# r3_sch.net
KiCad netlist of a schematic drawn in EAGLE
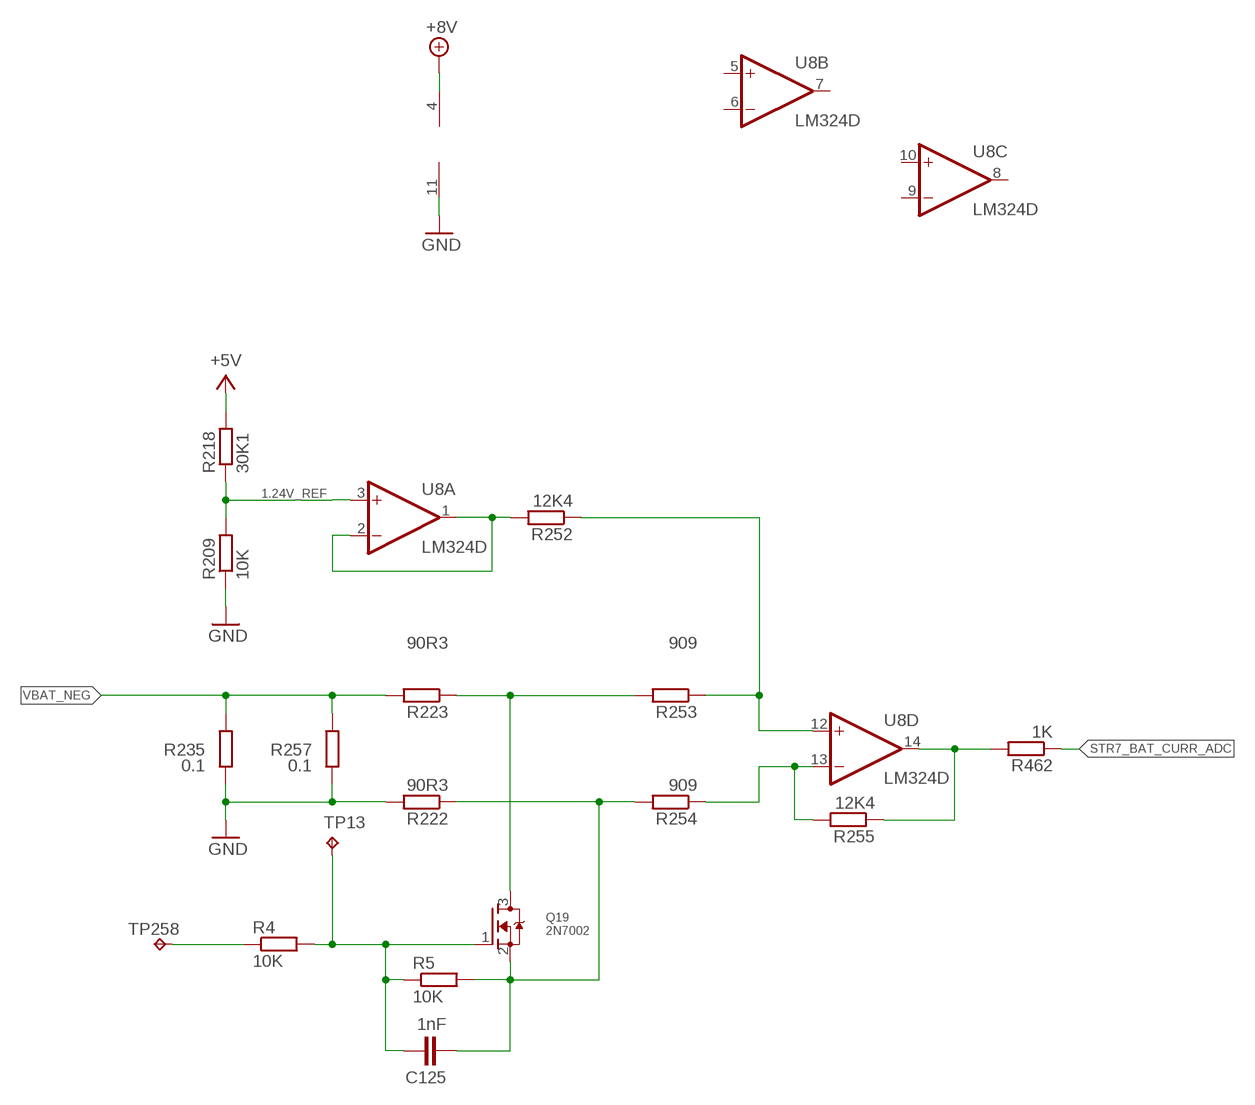
[diagram p0: schematic, sheet 1]

(export (version "E")
  (design (tool "Eeschema 10.0.6"))
  (components
    (comp (ref "C125")
      (value "1nF")
      (footprint "eagle-import:C0603")
      (libsource (lib "eagle-import") (part "C-EUC0603"))
    )
    (comp (ref "Q19")
      (value "2N7002")
      (footprint "eagle-import:SOT23")
      (libsource (lib "eagle-import") (part "MOSFET-NREFLOW"))
    )
    (comp (ref "R4")
      (value "10K")
      (footprint "eagle-import:R0603")
      (libsource (lib "eagle-import") (part "resistor_R-EU_R0603"))
    )
    (comp (ref "R5")
      (value "10K")
      (footprint "eagle-import:R0603")
      (libsource (lib "eagle-import") (part "resistor_R-EU_R0603"))
    )
    (comp (ref "R209")
      (value "10K")
      (footprint "eagle-import:R0603")
      (libsource (lib "eagle-import") (part "resistor_R-EU_R0603"))
    )
    (comp (ref "R218")
      (value "30K1")
      (footprint "eagle-import:R0603")
      (libsource (lib "eagle-import") (part "resistor_R-EU_R0603"))
    )
    (comp (ref "R222")
      (value "90R3")
      (footprint "eagle-import:R0603")
      (libsource (lib "eagle-import") (part "resistor_R-EU_R0603"))
    )
    (comp (ref "R223")
      (value "90R3")
      (footprint "eagle-import:R0603")
      (libsource (lib "eagle-import") (part "resistor_R-EU_R0603"))
    )
    (comp (ref "R235")
      (value "0.1")
      (footprint "eagle-import:R1206")
      (libsource (lib "eagle-import") (part "R-EU_R1206"))
    )
    (comp (ref "R252")
      (value "12K4")
      (footprint "eagle-import:R0603")
      (libsource (lib "eagle-import") (part "resistor_R-EU_R0603"))
    )
    (comp (ref "R253")
      (value "909")
      (footprint "eagle-import:R0603")
      (libsource (lib "eagle-import") (part "resistor_R-EU_R0603"))
    )
    (comp (ref "R254")
      (value "909")
      (footprint "eagle-import:R0603")
      (libsource (lib "eagle-import") (part "resistor_R-EU_R0603"))
    )
    (comp (ref "R255")
      (value "12K4")
      (footprint "eagle-import:R0603")
      (libsource (lib "eagle-import") (part "resistor_R-EU_R0603"))
    )
    (comp (ref "R257")
      (value "0.1")
      (footprint "eagle-import:R1206")
      (libsource (lib "eagle-import") (part "R-EU_R1206"))
    )
    (comp (ref "R462")
      (value "1K")
      (footprint "eagle-import:R0603")
      (libsource (lib "eagle-import") (part "resistor_R-EU_R0603"))
    )
    (comp (ref "TP13")
      (value "TPB1,27")
      (footprint "eagle-import:B1,27")
      (libsource (lib "eagle-import") (part "TPB1,27"))
    )
    (comp (ref "TP258")
      (value "TPB1,27")
      (footprint "eagle-import:B1,27")
      (libsource (lib "eagle-import") (part "TPB1,27"))
    )
    (comp (ref "U8")
      (value "LM324D")
      (footprint "eagle-import:SO14")
      (libsource (lib "eagle-import") (part "LM324D"))
    )
  )
  (nets
    (net (code "1") (name "+5V") (class "Default")
      (node (ref "R218") (pin "2") (pinfunction "2_2") (pintype "passive"))
    )
    (net (code "2") (name "+8V") (class "Default")
      (node (ref "U8") (pin "4") (pinfunction "V+_4") (pintype "power_in"))
    )
    (net (code "3") (name "/1.24V_REF") (class "Default")
      (node (ref "R209") (pin "2") (pinfunction "2_2") (pintype "passive"))
      (node (ref "R218") (pin "1") (pinfunction "1_1") (pintype "passive"))
      (node (ref "U8") (pin "3") (pinfunction "+IN_3") (pintype "input"))
    )
    (net (code "4") (name "GND") (class "Default")
      (node (ref "R209") (pin "1") (pinfunction "1_1") (pintype "passive"))
      (node (ref "R222") (pin "2") (pinfunction "2_2") (pintype "passive"))
      (node (ref "R235") (pin "2") (pinfunction "2_2") (pintype "passive"))
      (node (ref "R257") (pin "2") (pinfunction "2_2") (pintype "passive"))
      (node (ref "U8") (pin "11") (pinfunction "V-_11") (pintype "power_in"))
    )
    (net (code "5") (name "Net-(Q19-D)") (class "Default")
      (node (ref "Q19") (pin "3") (pinfunction "D_3") (pintype "bidirectional"))
      (node (ref "R223") (pin "1") (pinfunction "1_1") (pintype "passive"))
      (node (ref "R253") (pin "2") (pinfunction "2_2") (pintype "passive"))
    )
    (net (code "6") (name "Net-(Q19-G)") (class "Default")
      (node (ref "C125") (pin "1") (pinfunction "1_1") (pintype "passive"))
      (node (ref "Q19") (pin "1") (pinfunction "G_1") (pintype "bidirectional"))
      (node (ref "R4") (pin "2") (pinfunction "2_2") (pintype "passive"))
      (node (ref "R5") (pin "1") (pinfunction "1_1") (pintype "passive"))
      (node (ref "TP13") (pin "TP") (pinfunction "TP_TP") (pintype "input"))
    )
    (net (code "7") (name "Net-(Q19-S)") (class "Default")
      (node (ref "C125") (pin "2") (pinfunction "2_2") (pintype "passive"))
      (node (ref "Q19") (pin "2") (pinfunction "S_2") (pintype "bidirectional"))
      (node (ref "R222") (pin "1") (pinfunction "1_1") (pintype "passive"))
      (node (ref "R254") (pin "2") (pinfunction "2_2") (pintype "passive"))
      (node (ref "R5") (pin "2") (pinfunction "2_2") (pintype "passive"))
    )
    (net (code "8") (name "Net-(R4-Pad1)") (class "Default")
      (node (ref "R4") (pin "1") (pinfunction "1_1") (pintype "passive"))
      (node (ref "TP258") (pin "TP") (pinfunction "TP_TP") (pintype "input"))
    )
    (net (code "9") (name "Net-(U8A--IN)") (class "Default")
      (node (ref "R252") (pin "2") (pinfunction "2_2") (pintype "passive"))
      (node (ref "U8") (pin "1") (pinfunction "OUT_1") (pintype "output"))
      (node (ref "U8") (pin "2") (pinfunction "-IN_2") (pintype "input"))
    )
    (net (code "10") (name "Net-(U8D-+IN)") (class "Default")
      (node (ref "R252") (pin "1") (pinfunction "1_1") (pintype "passive"))
      (node (ref "R253") (pin "1") (pinfunction "1_1") (pintype "passive"))
      (node (ref "U8") (pin "12") (pinfunction "+IN_12") (pintype "input"))
    )
    (net (code "11") (name "Net-(U8D--IN)") (class "Default")
      (node (ref "R254") (pin "1") (pinfunction "1_1") (pintype "passive"))
      (node (ref "R255") (pin "2") (pinfunction "2_2") (pintype "passive"))
      (node (ref "U8") (pin "13") (pinfunction "-IN_13") (pintype "input"))
    )
    (net (code "12") (name "Net-(U8D-OUT)") (class "Default")
      (node (ref "R255") (pin "1") (pinfunction "1_1") (pintype "passive"))
      (node (ref "R462") (pin "2") (pinfunction "2_2") (pintype "passive"))
      (node (ref "U8") (pin "14") (pinfunction "OUT_14") (pintype "output"))
    )
    (net (code "13") (name "STR7_BAT_CURR_ADC") (class "Default")
      (node (ref "R462") (pin "1") (pinfunction "1_1") (pintype "passive"))
    )
    (net (code "14") (name "VBAT_NEG") (class "Default")
      (node (ref "R223") (pin "2") (pinfunction "2_2") (pintype "passive"))
      (node (ref "R235") (pin "1") (pinfunction "1_1") (pintype "passive"))
      (node (ref "R257") (pin "1") (pinfunction "1_1") (pintype "passive"))
    )
    (net (code "15") (name "unconnected-(U8B-+IN-Pad5)") (class "Default")
      (node (ref "U8") (pin "5") (pinfunction "+IN_5") (pintype "input"))
    )
    (net (code "16") (name "unconnected-(U8B--IN-Pad6)") (class "Default")
      (node (ref "U8") (pin "6") (pinfunction "-IN_6") (pintype "input"))
    )
    (net (code "17") (name "unconnected-(U8B-OUT-Pad7)") (class "Default")
      (node (ref "U8") (pin "7") (pinfunction "OUT_7") (pintype "output"))
    )
    (net (code "18") (name "unconnected-(U8C-+IN-Pad10)") (class "Default")
      (node (ref "U8") (pin "10") (pinfunction "+IN_10") (pintype "input"))
    )
    (net (code "19") (name "unconnected-(U8C--IN-Pad9)") (class "Default")
      (node (ref "U8") (pin "9") (pinfunction "-IN_9") (pintype "input"))
    )
    (net (code "20") (name "unconnected-(U8C-OUT-Pad8)") (class "Default")
      (node (ref "U8") (pin "8") (pinfunction "OUT_8") (pintype "output"))
    )
  )
)
